# W101B.net
KiCad netlist of a schematic drawn in EAGLE
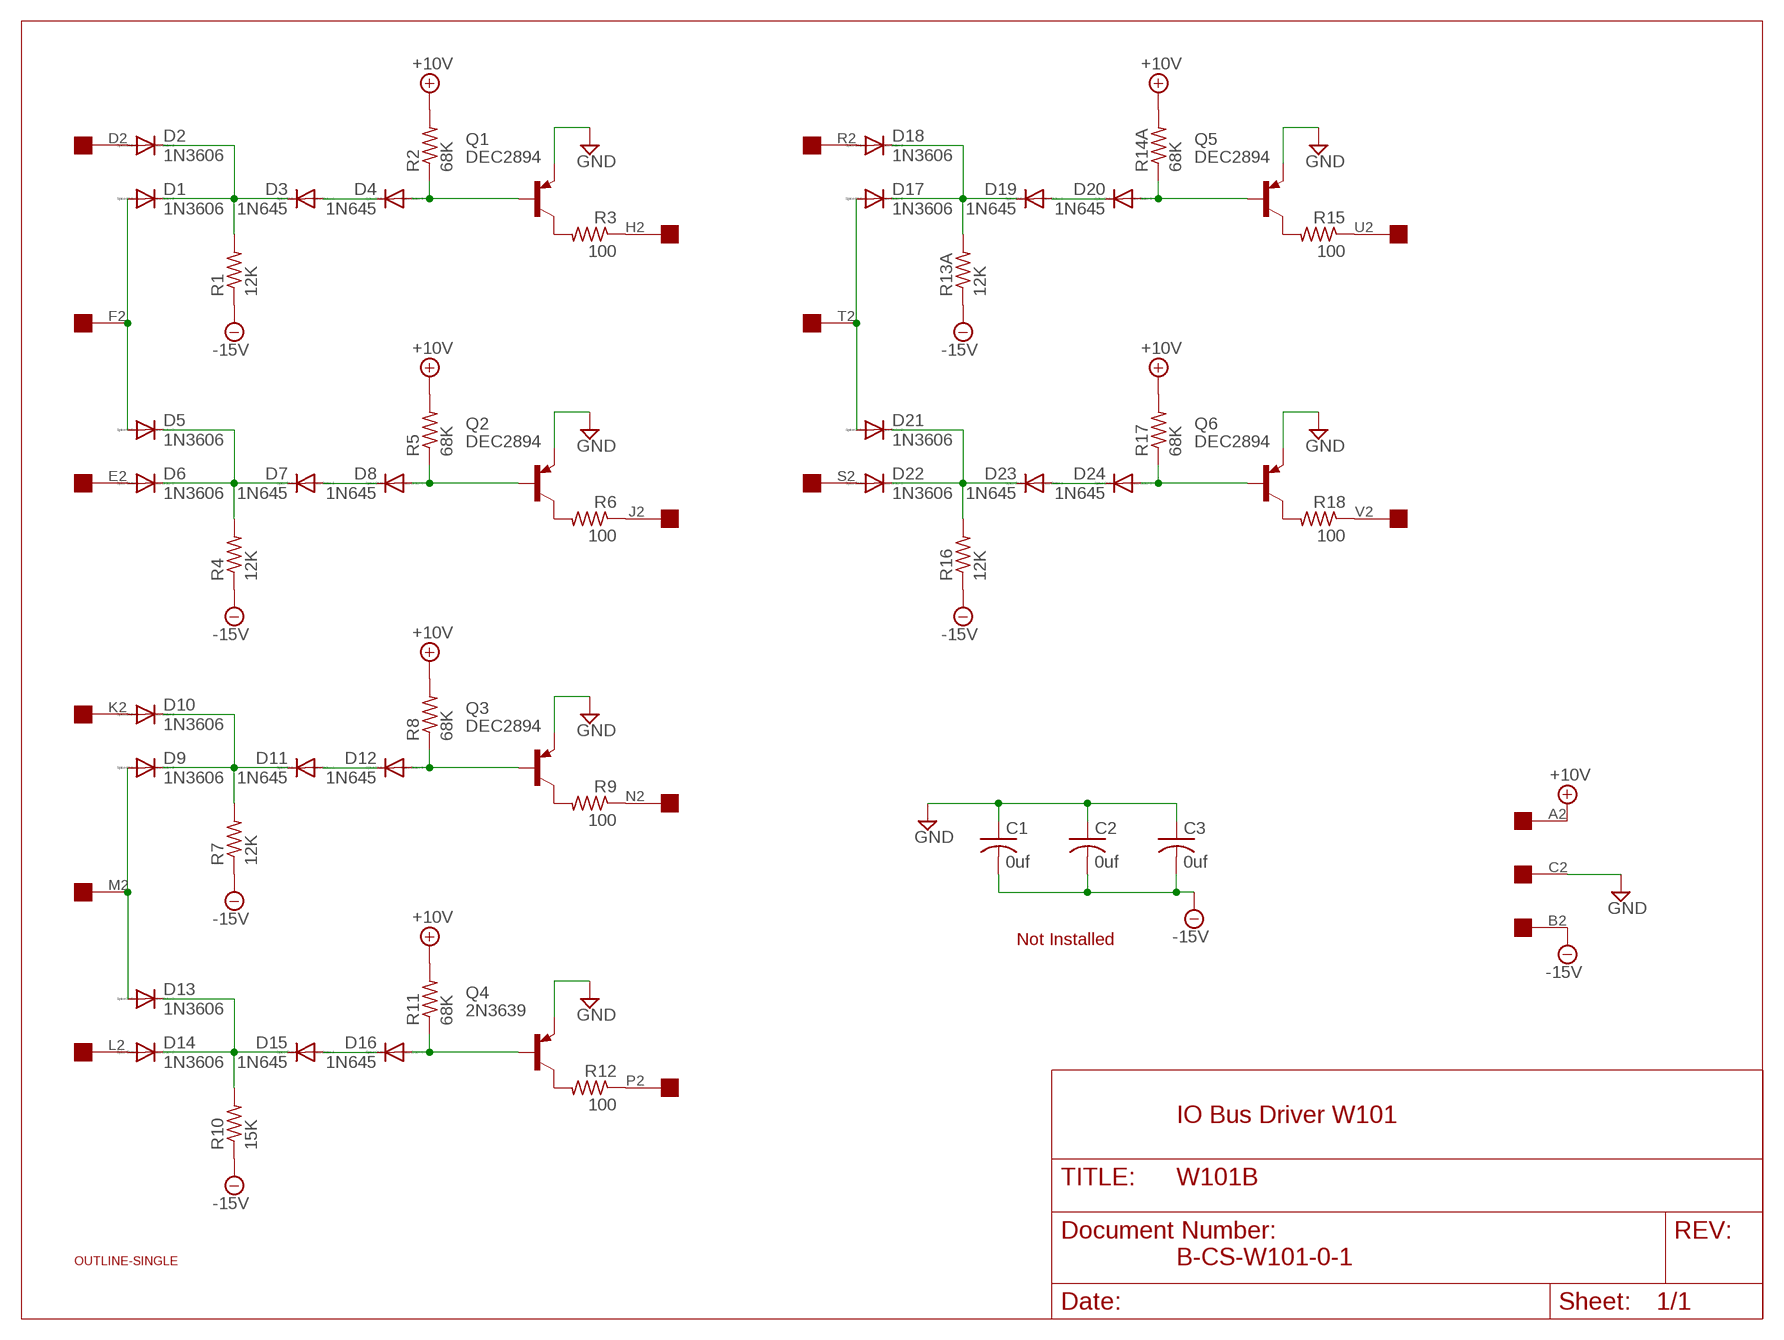
[diagram p0: schematic, sheet 1]

(export (version "E")
  (design (tool "Eeschema 10.0.6"))
  (components
    (comp (ref "C1")
      (value "0uf")
      (footprint "eagle-import:C050-025X075")
      (libsource (lib "eagle-import") (part "C-US050-025X075"))
    )
    (comp (ref "C2")
      (value "0uf")
      (footprint "eagle-import:C050-025X075")
      (libsource (lib "eagle-import") (part "C-US050-025X075"))
    )
    (comp (ref "C3")
      (value "0uf")
      (footprint "eagle-import:C050-025X075")
      (libsource (lib "eagle-import") (part "C-US050-025X075"))
    )
    (comp (ref "D1")
      (value "1N3606")
      (footprint "eagle-import:DO35-10")
      (libsource (lib "eagle-import") (part "1N4148DO35-10"))
    )
    (comp (ref "D2")
      (value "1N3606")
      (footprint "eagle-import:DO35-10")
      (libsource (lib "eagle-import") (part "1N4148DO35-10"))
    )
    (comp (ref "D3")
      (value "1N645")
      (footprint "eagle-import:DO35-10")
      (libsource (lib "eagle-import") (part "1N4148DO35-10"))
    )
    (comp (ref "D4")
      (value "1N645")
      (footprint "eagle-import:DO35-10")
      (libsource (lib "eagle-import") (part "1N4148DO35-10"))
    )
    (comp (ref "D5")
      (value "1N3606")
      (footprint "eagle-import:DO35-10")
      (libsource (lib "eagle-import") (part "1N4148DO35-10"))
    )
    (comp (ref "D6")
      (value "1N3606")
      (footprint "eagle-import:DO35-10")
      (libsource (lib "eagle-import") (part "1N4148DO35-10"))
    )
    (comp (ref "D7")
      (value "1N645")
      (footprint "eagle-import:DO35-10")
      (libsource (lib "eagle-import") (part "1N4148DO35-10"))
    )
    (comp (ref "D8")
      (value "1N645")
      (footprint "eagle-import:DO35-10")
      (libsource (lib "eagle-import") (part "1N4148DO35-10"))
    )
    (comp (ref "D9")
      (value "1N3606")
      (footprint "eagle-import:DO35-10")
      (libsource (lib "eagle-import") (part "1N4148DO35-10"))
    )
    (comp (ref "D10")
      (value "1N3606")
      (footprint "eagle-import:DO35-10")
      (libsource (lib "eagle-import") (part "1N4148DO35-10"))
    )
    (comp (ref "D11")
      (value "1N645")
      (footprint "eagle-import:DO35-10")
      (libsource (lib "eagle-import") (part "1N4148DO35-10"))
    )
    (comp (ref "D12")
      (value "1N645")
      (footprint "eagle-import:DO35-10")
      (libsource (lib "eagle-import") (part "1N4148DO35-10"))
    )
    (comp (ref "D13")
      (value "1N3606")
      (footprint "eagle-import:DO35-10")
      (libsource (lib "eagle-import") (part "1N4148DO35-10"))
    )
    (comp (ref "D14")
      (value "1N3606")
      (footprint "eagle-import:DO35-10")
      (libsource (lib "eagle-import") (part "1N4148DO35-10"))
    )
    (comp (ref "D15")
      (value "1N645")
      (footprint "eagle-import:DO35-10")
      (libsource (lib "eagle-import") (part "1N4148DO35-10"))
    )
    (comp (ref "D16")
      (value "1N645")
      (footprint "eagle-import:DO35-10")
      (libsource (lib "eagle-import") (part "1N4148DO35-10"))
    )
    (comp (ref "D17")
      (value "1N3606")
      (footprint "eagle-import:DO35-10")
      (libsource (lib "eagle-import") (part "1N4148DO35-10"))
    )
    (comp (ref "D18")
      (value "1N3606")
      (footprint "eagle-import:DO35-10")
      (libsource (lib "eagle-import") (part "1N4148DO35-10"))
    )
    (comp (ref "D19")
      (value "1N645")
      (footprint "eagle-import:DO35-10")
      (libsource (lib "eagle-import") (part "1N4148DO35-10"))
    )
    (comp (ref "D20")
      (value "1N645")
      (footprint "eagle-import:DO35-10")
      (libsource (lib "eagle-import") (part "1N4148DO35-10"))
    )
    (comp (ref "D21")
      (value "1N3606")
      (footprint "eagle-import:DO35-10")
      (libsource (lib "eagle-import") (part "1N4148DO35-10"))
    )
    (comp (ref "D22")
      (value "1N3606")
      (footprint "eagle-import:DO35-10")
      (libsource (lib "eagle-import") (part "1N4148DO35-10"))
    )
    (comp (ref "D23")
      (value "1N645")
      (footprint "eagle-import:DO35-10")
      (libsource (lib "eagle-import") (part "1N4148DO35-10"))
    )
    (comp (ref "D24")
      (value "1N645")
      (footprint "eagle-import:DO35-10")
      (libsource (lib "eagle-import") (part "1N4148DO35-10"))
    )
    (comp (ref "Q1")
      (value "DEC2894")
      (footprint "eagle-import:TO39")
      (libsource (lib "eagle-import") (part "2N3637"))
    )
    (comp (ref "Q2")
      (value "DEC2894")
      (footprint "eagle-import:TO39")
      (libsource (lib "eagle-import") (part "2N3637"))
    )
    (comp (ref "Q3")
      (value "DEC2894")
      (footprint "eagle-import:TO39")
      (libsource (lib "eagle-import") (part "2N3637"))
    )
    (comp (ref "Q4")
      (value "2N3639")
      (footprint "eagle-import:TO39")
      (libsource (lib "eagle-import") (part "2N3637"))
    )
    (comp (ref "Q5")
      (value "DEC2894")
      (footprint "eagle-import:TO39")
      (libsource (lib "eagle-import") (part "2N3637"))
    )
    (comp (ref "Q6")
      (value "DEC2894")
      (footprint "eagle-import:TO39")
      (libsource (lib "eagle-import") (part "2N3637"))
    )
    (comp (ref "R1")
      (value "12K")
      (footprint "eagle-import:0207_10")
      (libsource (lib "eagle-import") (part "R-US_0207/10"))
    )
    (comp (ref "R2")
      (value "68K")
      (footprint "eagle-import:0207_10")
      (libsource (lib "eagle-import") (part "R-US_0207/10"))
    )
    (comp (ref "R3")
      (value "100")
      (footprint "eagle-import:0207_10")
      (libsource (lib "eagle-import") (part "R-US_0207/10"))
    )
    (comp (ref "R4")
      (value "12K")
      (footprint "eagle-import:0207_10")
      (libsource (lib "eagle-import") (part "R-US_0207/10"))
    )
    (comp (ref "R5")
      (value "68K")
      (footprint "eagle-import:0207_10")
      (libsource (lib "eagle-import") (part "R-US_0207/10"))
    )
    (comp (ref "R6")
      (value "100")
      (footprint "eagle-import:0207_10")
      (libsource (lib "eagle-import") (part "R-US_0207/10"))
    )
    (comp (ref "R7")
      (value "12K")
      (footprint "eagle-import:0207_10")
      (libsource (lib "eagle-import") (part "R-US_0207/10"))
    )
    (comp (ref "R8")
      (value "68K")
      (footprint "eagle-import:0207_10")
      (libsource (lib "eagle-import") (part "R-US_0207/10"))
    )
    (comp (ref "R9")
      (value "100")
      (footprint "eagle-import:0207_10")
      (libsource (lib "eagle-import") (part "R-US_0207/10"))
    )
    (comp (ref "R10")
      (value "15K")
      (footprint "eagle-import:0207_10")
      (libsource (lib "eagle-import") (part "R-US_0207/10"))
    )
    (comp (ref "R11")
      (value "68K")
      (footprint "eagle-import:0207_10")
      (libsource (lib "eagle-import") (part "R-US_0207/10"))
    )
    (comp (ref "R12")
      (value "100")
      (footprint "eagle-import:0207_10")
      (libsource (lib "eagle-import") (part "R-US_0207/10"))
    )
    (comp (ref "R13A")
      (value "12K")
      (footprint "eagle-import:0207_10")
      (libsource (lib "eagle-import") (part "R-US_0207/10"))
    )
    (comp (ref "R14A")
      (value "68K")
      (footprint "eagle-import:0207_10")
      (libsource (lib "eagle-import") (part "R-US_0207/10"))
    )
    (comp (ref "R15")
      (value "100")
      (footprint "eagle-import:0207_10")
      (libsource (lib "eagle-import") (part "R-US_0207/10"))
    )
    (comp (ref "R16")
      (value "12K")
      (footprint "eagle-import:0207_10")
      (libsource (lib "eagle-import") (part "R-US_0207/10"))
    )
    (comp (ref "R17")
      (value "68K")
      (footprint "eagle-import:0207_10")
      (libsource (lib "eagle-import") (part "R-US_0207/10"))
    )
    (comp (ref "R18")
      (value "100")
      (footprint "eagle-import:0207_10")
      (libsource (lib "eagle-import") (part "R-US_0207/10"))
    )
    (comp (ref "U$1")
      (value "OUTLINE-SINGLE")
      (footprint "eagle-import:SINGLE")
      (libsource (lib "eagle-import") (part "OUTLINE-SINGLE"))
    )
    (comp (ref "U$2")
      (value "EDGE-1")
      (footprint "eagle-import:EDGE-CON1")
      (libsource (lib "eagle-import") (part "EDGE-1"))
    )
  )
  (nets
    (net (code "1") (name "+10V") (class "Default")
      (node (ref "R11") (pin "2") (pinfunction "2_2") (pintype "passive"))
      (node (ref "R14A") (pin "2") (pinfunction "2_2") (pintype "passive"))
      (node (ref "R17") (pin "2") (pinfunction "2_2") (pintype "passive"))
      (node (ref "R2") (pin "2") (pinfunction "2_2") (pintype "passive"))
      (node (ref "R5") (pin "2") (pinfunction "2_2") (pintype "passive"))
      (node (ref "R8") (pin "2") (pinfunction "2_2") (pintype "passive"))
      (node (ref "U$2") (pin "A2") (pinfunction "1_A2") (pintype "bidirectional"))
    )
    (net (code "2") (name "-15V") (class "Default")
      (node (ref "C1") (pin "2") (pinfunction "2_2") (pintype "passive"))
      (node (ref "C2") (pin "2") (pinfunction "2_2") (pintype "passive"))
      (node (ref "C3") (pin "2") (pinfunction "2_2") (pintype "passive"))
      (node (ref "R1") (pin "1") (pinfunction "1_1") (pintype "passive"))
      (node (ref "R10") (pin "1") (pinfunction "1_1") (pintype "passive"))
      (node (ref "R13A") (pin "1") (pinfunction "1_1") (pintype "passive"))
      (node (ref "R16") (pin "1") (pinfunction "1_1") (pintype "passive"))
      (node (ref "R4") (pin "1") (pinfunction "1_1") (pintype "passive"))
      (node (ref "R7") (pin "1") (pinfunction "1_1") (pintype "passive"))
      (node (ref "U$2") (pin "B2") (pinfunction "1_B2") (pintype "bidirectional"))
    )
    (net (code "3") (name "GND") (class "Default")
      (node (ref "C1") (pin "1") (pinfunction "1_1") (pintype "passive"))
      (node (ref "C2") (pin "1") (pinfunction "1_1") (pintype "passive"))
      (node (ref "C3") (pin "1") (pinfunction "1_1") (pintype "passive"))
      (node (ref "Q1") (pin "1") (pinfunction "E_1") (pintype "passive"))
      (node (ref "Q2") (pin "1") (pinfunction "E_1") (pintype "passive"))
      (node (ref "Q3") (pin "1") (pinfunction "E_1") (pintype "passive"))
      (node (ref "Q4") (pin "1") (pinfunction "E_1") (pintype "passive"))
      (node (ref "Q5") (pin "1") (pinfunction "E_1") (pintype "passive"))
      (node (ref "Q6") (pin "1") (pinfunction "E_1") (pintype "passive"))
      (node (ref "U$2") (pin "C2") (pinfunction "1_C2") (pintype "bidirectional"))
    )
    (net (code "4") (name "Net-(D1-PadC)") (class "Default")
      (node (ref "D1") (pin "C") (pinfunction "C_C") (pintype "passive"))
      (node (ref "D2") (pin "C") (pinfunction "C_C") (pintype "passive"))
      (node (ref "D3") (pin "C") (pinfunction "C_C") (pintype "passive"))
      (node (ref "R1") (pin "2") (pinfunction "2_2") (pintype "passive"))
    )
    (net (code "5") (name "Net-(D3-PadA)") (class "Default")
      (node (ref "D3") (pin "A") (pinfunction "A_A") (pintype "passive"))
      (node (ref "D4") (pin "C") (pinfunction "C_C") (pintype "passive"))
    )
    (net (code "6") (name "Net-(D5-PadC)") (class "Default")
      (node (ref "D5") (pin "C") (pinfunction "C_C") (pintype "passive"))
      (node (ref "D6") (pin "C") (pinfunction "C_C") (pintype "passive"))
      (node (ref "D7") (pin "C") (pinfunction "C_C") (pintype "passive"))
      (node (ref "R4") (pin "2") (pinfunction "2_2") (pintype "passive"))
    )
    (net (code "7") (name "Net-(D7-PadA)") (class "Default")
      (node (ref "D7") (pin "A") (pinfunction "A_A") (pintype "passive"))
      (node (ref "D8") (pin "C") (pinfunction "C_C") (pintype "passive"))
    )
    (net (code "8") (name "Net-(D10-PadC)") (class "Default")
      (node (ref "D10") (pin "C") (pinfunction "C_C") (pintype "passive"))
      (node (ref "D11") (pin "C") (pinfunction "C_C") (pintype "passive"))
      (node (ref "D9") (pin "C") (pinfunction "C_C") (pintype "passive"))
      (node (ref "R7") (pin "2") (pinfunction "2_2") (pintype "passive"))
    )
    (net (code "9") (name "Net-(D11-PadA)") (class "Default")
      (node (ref "D11") (pin "A") (pinfunction "A_A") (pintype "passive"))
      (node (ref "D12") (pin "C") (pinfunction "C_C") (pintype "passive"))
    )
    (net (code "10") (name "Net-(D13-PadC)") (class "Default")
      (node (ref "D13") (pin "C") (pinfunction "C_C") (pintype "passive"))
      (node (ref "D14") (pin "C") (pinfunction "C_C") (pintype "passive"))
      (node (ref "D15") (pin "C") (pinfunction "C_C") (pintype "passive"))
      (node (ref "R10") (pin "2") (pinfunction "2_2") (pintype "passive"))
    )
    (net (code "11") (name "Net-(D15-PadA)") (class "Default")
      (node (ref "D15") (pin "A") (pinfunction "A_A") (pintype "passive"))
      (node (ref "D16") (pin "C") (pinfunction "C_C") (pintype "passive"))
    )
    (net (code "12") (name "Net-(D17-PadC)") (class "Default")
      (node (ref "D17") (pin "C") (pinfunction "C_C") (pintype "passive"))
      (node (ref "D18") (pin "C") (pinfunction "C_C") (pintype "passive"))
      (node (ref "D19") (pin "C") (pinfunction "C_C") (pintype "passive"))
      (node (ref "R13A") (pin "2") (pinfunction "2_2") (pintype "passive"))
    )
    (net (code "13") (name "Net-(D19-PadA)") (class "Default")
      (node (ref "D19") (pin "A") (pinfunction "A_A") (pintype "passive"))
      (node (ref "D20") (pin "C") (pinfunction "C_C") (pintype "passive"))
    )
    (net (code "14") (name "Net-(D21-PadC)") (class "Default")
      (node (ref "D21") (pin "C") (pinfunction "C_C") (pintype "passive"))
      (node (ref "D22") (pin "C") (pinfunction "C_C") (pintype "passive"))
      (node (ref "D23") (pin "C") (pinfunction "C_C") (pintype "passive"))
      (node (ref "R16") (pin "2") (pinfunction "2_2") (pintype "passive"))
    )
    (net (code "15") (name "Net-(D23-PadA)") (class "Default")
      (node (ref "D23") (pin "A") (pinfunction "A_A") (pintype "passive"))
      (node (ref "D24") (pin "C") (pinfunction "C_C") (pintype "passive"))
    )
    (net (code "16") (name "Net-(Q1-B)") (class "Default")
      (node (ref "D4") (pin "A") (pinfunction "A_A") (pintype "passive"))
      (node (ref "Q1") (pin "2") (pinfunction "B_2") (pintype "passive"))
      (node (ref "R2") (pin "1") (pinfunction "1_1") (pintype "passive"))
    )
    (net (code "17") (name "Net-(Q1-C)") (class "Default")
      (node (ref "Q1") (pin "3") (pinfunction "C_3") (pintype "passive"))
      (node (ref "R3") (pin "2") (pinfunction "2_2") (pintype "passive"))
    )
    (net (code "18") (name "Net-(Q2-B)") (class "Default")
      (node (ref "D8") (pin "A") (pinfunction "A_A") (pintype "passive"))
      (node (ref "Q2") (pin "2") (pinfunction "B_2") (pintype "passive"))
      (node (ref "R5") (pin "1") (pinfunction "1_1") (pintype "passive"))
    )
    (net (code "19") (name "Net-(Q2-C)") (class "Default")
      (node (ref "Q2") (pin "3") (pinfunction "C_3") (pintype "passive"))
      (node (ref "R6") (pin "2") (pinfunction "2_2") (pintype "passive"))
    )
    (net (code "20") (name "Net-(Q3-B)") (class "Default")
      (node (ref "D12") (pin "A") (pinfunction "A_A") (pintype "passive"))
      (node (ref "Q3") (pin "2") (pinfunction "B_2") (pintype "passive"))
      (node (ref "R8") (pin "1") (pinfunction "1_1") (pintype "passive"))
    )
    (net (code "21") (name "Net-(Q3-C)") (class "Default")
      (node (ref "Q3") (pin "3") (pinfunction "C_3") (pintype "passive"))
      (node (ref "R9") (pin "2") (pinfunction "2_2") (pintype "passive"))
    )
    (net (code "22") (name "Net-(Q4-B)") (class "Default")
      (node (ref "D16") (pin "A") (pinfunction "A_A") (pintype "passive"))
      (node (ref "Q4") (pin "2") (pinfunction "B_2") (pintype "passive"))
      (node (ref "R11") (pin "1") (pinfunction "1_1") (pintype "passive"))
    )
    (net (code "23") (name "Net-(Q4-C)") (class "Default")
      (node (ref "Q4") (pin "3") (pinfunction "C_3") (pintype "passive"))
      (node (ref "R12") (pin "2") (pinfunction "2_2") (pintype "passive"))
    )
    (net (code "24") (name "Net-(Q5-B)") (class "Default")
      (node (ref "D20") (pin "A") (pinfunction "A_A") (pintype "passive"))
      (node (ref "Q5") (pin "2") (pinfunction "B_2") (pintype "passive"))
      (node (ref "R14A") (pin "1") (pinfunction "1_1") (pintype "passive"))
    )
    (net (code "25") (name "Net-(Q5-C)") (class "Default")
      (node (ref "Q5") (pin "3") (pinfunction "C_3") (pintype "passive"))
      (node (ref "R15") (pin "2") (pinfunction "2_2") (pintype "passive"))
    )
    (net (code "26") (name "Net-(Q6-B)") (class "Default")
      (node (ref "D24") (pin "A") (pinfunction "A_A") (pintype "passive"))
      (node (ref "Q6") (pin "2") (pinfunction "B_2") (pintype "passive"))
      (node (ref "R17") (pin "1") (pinfunction "1_1") (pintype "passive"))
    )
    (net (code "27") (name "Net-(Q6-C)") (class "Default")
      (node (ref "Q6") (pin "3") (pinfunction "C_3") (pintype "passive"))
      (node (ref "R18") (pin "2") (pinfunction "2_2") (pintype "passive"))
    )
    (net (code "28") (name "Net-(U$2D-1)") (class "Default")
      (node (ref "D2") (pin "A") (pinfunction "A_A") (pintype "passive"))
      (node (ref "U$2") (pin "D2") (pinfunction "1_D2") (pintype "bidirectional"))
    )
    (net (code "29") (name "Net-(U$2E-1)") (class "Default")
      (node (ref "D6") (pin "A") (pinfunction "A_A") (pintype "passive"))
      (node (ref "U$2") (pin "E2") (pinfunction "1_E2") (pintype "bidirectional"))
    )
    (net (code "30") (name "Net-(U$2F-1)") (class "Default")
      (node (ref "D1") (pin "A") (pinfunction "A_A") (pintype "passive"))
      (node (ref "D5") (pin "A") (pinfunction "A_A") (pintype "passive"))
      (node (ref "U$2") (pin "F2") (pinfunction "1_F2") (pintype "bidirectional"))
    )
    (net (code "31") (name "Net-(U$2G-1)") (class "Default")
      (node (ref "R3") (pin "1") (pinfunction "1_1") (pintype "passive"))
      (node (ref "U$2") (pin "H2") (pinfunction "1_H2") (pintype "bidirectional"))
    )
    (net (code "32") (name "Net-(U$2H-1)") (class "Default")
      (node (ref "R6") (pin "1") (pinfunction "1_1") (pintype "passive"))
      (node (ref "U$2") (pin "J2") (pinfunction "1_J2") (pintype "bidirectional"))
    )
    (net (code "33") (name "Net-(U$2I-1)") (class "Default")
      (node (ref "D10") (pin "A") (pinfunction "A_A") (pintype "passive"))
      (node (ref "U$2") (pin "K2") (pinfunction "1_K2") (pintype "bidirectional"))
    )
    (net (code "34") (name "Net-(U$2J-1)") (class "Default")
      (node (ref "D14") (pin "A") (pinfunction "A_A") (pintype "passive"))
      (node (ref "U$2") (pin "L2") (pinfunction "1_L2") (pintype "bidirectional"))
    )
    (net (code "35") (name "Net-(U$2K-1)") (class "Default")
      (node (ref "D13") (pin "A") (pinfunction "A_A") (pintype "passive"))
      (node (ref "D9") (pin "A") (pinfunction "A_A") (pintype "passive"))
      (node (ref "U$2") (pin "M2") (pinfunction "1_M2") (pintype "bidirectional"))
    )
    (net (code "36") (name "Net-(U$2L-1)") (class "Default")
      (node (ref "R9") (pin "1") (pinfunction "1_1") (pintype "passive"))
      (node (ref "U$2") (pin "N2") (pinfunction "1_N2") (pintype "bidirectional"))
    )
    (net (code "37") (name "Net-(U$2M-1)") (class "Default")
      (node (ref "R12") (pin "1") (pinfunction "1_1") (pintype "passive"))
      (node (ref "U$2") (pin "P2") (pinfunction "1_P2") (pintype "bidirectional"))
    )
    (net (code "38") (name "Net-(U$2N-1)") (class "Default")
      (node (ref "D18") (pin "A") (pinfunction "A_A") (pintype "passive"))
      (node (ref "U$2") (pin "R2") (pinfunction "1_R2") (pintype "bidirectional"))
    )
    (net (code "39") (name "Net-(U$2O-1)") (class "Default")
      (node (ref "D22") (pin "A") (pinfunction "A_A") (pintype "passive"))
      (node (ref "U$2") (pin "S2") (pinfunction "1_S2") (pintype "bidirectional"))
    )
    (net (code "40") (name "Net-(U$2P-1)") (class "Default")
      (node (ref "D17") (pin "A") (pinfunction "A_A") (pintype "passive"))
      (node (ref "D21") (pin "A") (pinfunction "A_A") (pintype "passive"))
      (node (ref "U$2") (pin "T2") (pinfunction "1_T2") (pintype "bidirectional"))
    )
    (net (code "41") (name "Net-(U$2Q-1)") (class "Default")
      (node (ref "R15") (pin "1") (pinfunction "1_1") (pintype "passive"))
      (node (ref "U$2") (pin "U2") (pinfunction "1_U2") (pintype "bidirectional"))
    )
    (net (code "42") (name "Net-(U$2R-1)") (class "Default")
      (node (ref "R18") (pin "1") (pinfunction "1_1") (pintype "passive"))
      (node (ref "U$2") (pin "V2") (pinfunction "1_V2") (pintype "bidirectional"))
    )
  )
)
